# teensy32_design_block.net
KiCad netlist of a schematic drawn in EAGLE
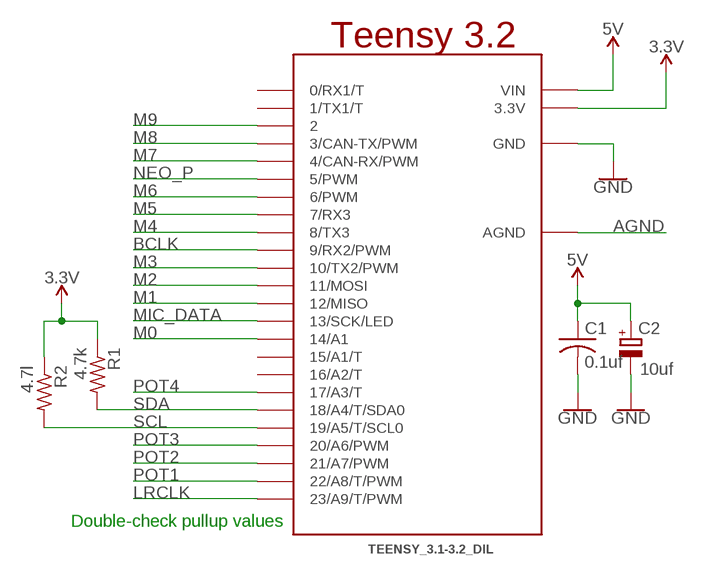
[diagram p0: schematic, sheet 1]

(export (version "E")
  (design (tool "Eeschema 10.0.6"))
  (components
    (comp (ref "C1")
      (value "0.1uf")
      (footprint "eagle-import:C0805K")
      (libsource (lib "eagle-import") (part "C-USC0805K"))
    )
    (comp (ref "C2")
      (value "10uf")
      (footprint "eagle-import:E2,5-7")
      (libsource (lib "eagle-import") (part "CPOL-EUE2.5-7"))
    )
    (comp (ref "R1")
      (value "4.7k")
      (footprint "eagle-import:R0805")
      (libsource (lib "eagle-import") (part "R-US_R0805"))
    )
    (comp (ref "R2")
      (value "4.7l")
      (footprint "eagle-import:R0805")
      (libsource (lib "eagle-import") (part "R-US_R0805"))
    )
    (comp (ref "U$3")
      (value "TEENSY_3.1-3.2_DIL")
      (footprint "eagle-import:TEENSY_3.0-3.2&LC_DIL")
      (libsource (lib "eagle-import") (part "TEENSY_3.1-3.2_DIL"))
    )
  )
  (nets
    (net (code "1") (name "/AGND") (class "Default")
      (node (ref "U$3") (pin "AGND") (pinfunction "AGND_AGND") (pintype "power_in"))
    )
    (net (code "2") (name "/BCLK") (class "Default")
      (node (ref "U$3") (pin "9") (pinfunction "9/RX2/PWM_9") (pintype "bidirectional"))
    )
    (net (code "3") (name "/LRCLK") (class "Default")
      (node (ref "U$3") (pin "23/A9") (pinfunction "23/A9/T/PWM_23/A9") (pintype "bidirectional"))
    )
    (net (code "4") (name "/M0") (class "Default")
      (node (ref "U$3") (pin "14/A0") (pinfunction "14/A1_14/A0") (pintype "bidirectional"))
    )
    (net (code "5") (name "/M1") (class "Default")
      (node (ref "U$3") (pin "12") (pinfunction "12/MISO_12") (pintype "bidirectional"))
    )
    (net (code "6") (name "/M2") (class "Default")
      (node (ref "U$3") (pin "11") (pinfunction "11/MOSI_11") (pintype "bidirectional"))
    )
    (net (code "7") (name "/M3") (class "Default")
      (node (ref "U$3") (pin "10") (pinfunction "10/TX2/PWM_10") (pintype "bidirectional"))
    )
    (net (code "8") (name "/M4") (class "Default")
      (node (ref "U$3") (pin "8") (pinfunction "8/TX3_8") (pintype "bidirectional"))
    )
    (net (code "9") (name "/M5") (class "Default")
      (node (ref "U$3") (pin "7") (pinfunction "7/RX3_7") (pintype "bidirectional"))
    )
    (net (code "10") (name "/M6") (class "Default")
      (node (ref "U$3") (pin "6") (pinfunction "6/PWM_6") (pintype "bidirectional"))
    )
    (net (code "11") (name "/M7") (class "Default")
      (node (ref "U$3") (pin "4") (pinfunction "4/CAN-RX/PWM_4") (pintype "bidirectional"))
    )
    (net (code "12") (name "/M8") (class "Default")
      (node (ref "U$3") (pin "3") (pinfunction "3/CAN-TX/PWM_3") (pintype "bidirectional"))
    )
    (net (code "13") (name "/M9") (class "Default")
      (node (ref "U$3") (pin "2") (pinfunction "2_2") (pintype "bidirectional"))
    )
    (net (code "14") (name "/MIC_DATA") (class "Default")
      (node (ref "U$3") (pin "13") (pinfunction "13/SCK/LED_13") (pintype "bidirectional"))
    )
    (net (code "15") (name "/NEO_P") (class "Default")
      (node (ref "U$3") (pin "5") (pinfunction "5/PWM_5") (pintype "bidirectional"))
    )
    (net (code "16") (name "/POT1") (class "Default")
      (node (ref "U$3") (pin "22/A8") (pinfunction "22/A8/T/PWM_22/A8") (pintype "bidirectional"))
    )
    (net (code "17") (name "/POT2") (class "Default")
      (node (ref "U$3") (pin "21/A7") (pinfunction "21/A7/PWM_21/A7") (pintype "bidirectional"))
    )
    (net (code "18") (name "/POT3") (class "Default")
      (node (ref "U$3") (pin "20/A6") (pinfunction "20/A6/PWM_20/A6") (pintype "bidirectional"))
    )
    (net (code "19") (name "/POT4") (class "Default")
      (node (ref "U$3") (pin "17/A3") (pinfunction "17/A3/T_17/A3") (pintype "bidirectional"))
    )
    (net (code "20") (name "/SCL") (class "Default")
      (node (ref "R2") (pin "2") (pinfunction "2_2") (pintype "passive"))
      (node (ref "U$3") (pin "19/A5") (pinfunction "19/A5/T/SCL0_19/A5") (pintype "bidirectional"))
    )
    (net (code "21") (name "/SDA") (class "Default")
      (node (ref "R1") (pin "2") (pinfunction "2_2") (pintype "passive"))
      (node (ref "U$3") (pin "18/A4") (pinfunction "18/A4/T/SDA0_18/A4") (pintype "bidirectional"))
    )
    (net (code "22") (name "3.3V") (class "Default")
      (node (ref "R1") (pin "1") (pinfunction "1_1") (pintype "passive"))
      (node (ref "R2") (pin "1") (pinfunction "1_1") (pintype "passive"))
      (node (ref "U$3") (pin "3.3V") (pinfunction "3.3V_3.3V") (pintype "power_in"))
    )
    (net (code "23") (name "5V") (class "Default")
      (node (ref "C1") (pin "1") (pinfunction "1_1") (pintype "passive"))
      (node (ref "C2") (pin "+") (pinfunction "+_+") (pintype "passive"))
      (node (ref "U$3") (pin "VIN") (pinfunction "VIN_VIN") (pintype "power_in"))
    )
    (net (code "24") (name "GND") (class "Default")
      (node (ref "C1") (pin "2") (pinfunction "2_2") (pintype "passive"))
      (node (ref "C2") (pin "-") (pinfunction "-_-") (pintype "passive"))
      (node (ref "U$3") (pin "GND") (pinfunction "GND_GND") (pintype "power_in"))
    )
    (net (code "25") (name "unconnected-(U$3-0{slash}RX1{slash}T-Pad0)") (class "Default")
      (node (ref "U$3") (pin "0") (pinfunction "0/RX1/T_0") (pintype "bidirectional"))
    )
    (net (code "26") (name "unconnected-(U$3-1{slash}TX1{slash}T-Pad1)") (class "Default")
      (node (ref "U$3") (pin "1") (pinfunction "1/TX1/T_1") (pintype "bidirectional"))
    )
    (net (code "27") (name "unconnected-(U$3-15{slash}A1{slash}T-Pad15{slash}A1)") (class "Default")
      (node (ref "U$3") (pin "15/A1") (pinfunction "15/A1/T_15/A1") (pintype "bidirectional"))
    )
    (net (code "28") (name "unconnected-(U$3-16{slash}A2{slash}T-Pad16{slash}A2)") (class "Default")
      (node (ref "U$3") (pin "16/A2") (pinfunction "16/A2/T_16/A2") (pintype "bidirectional"))
    )
  )
)
